# SiLPA.net
KiCad netlist of a schematic drawn in Altium Designer
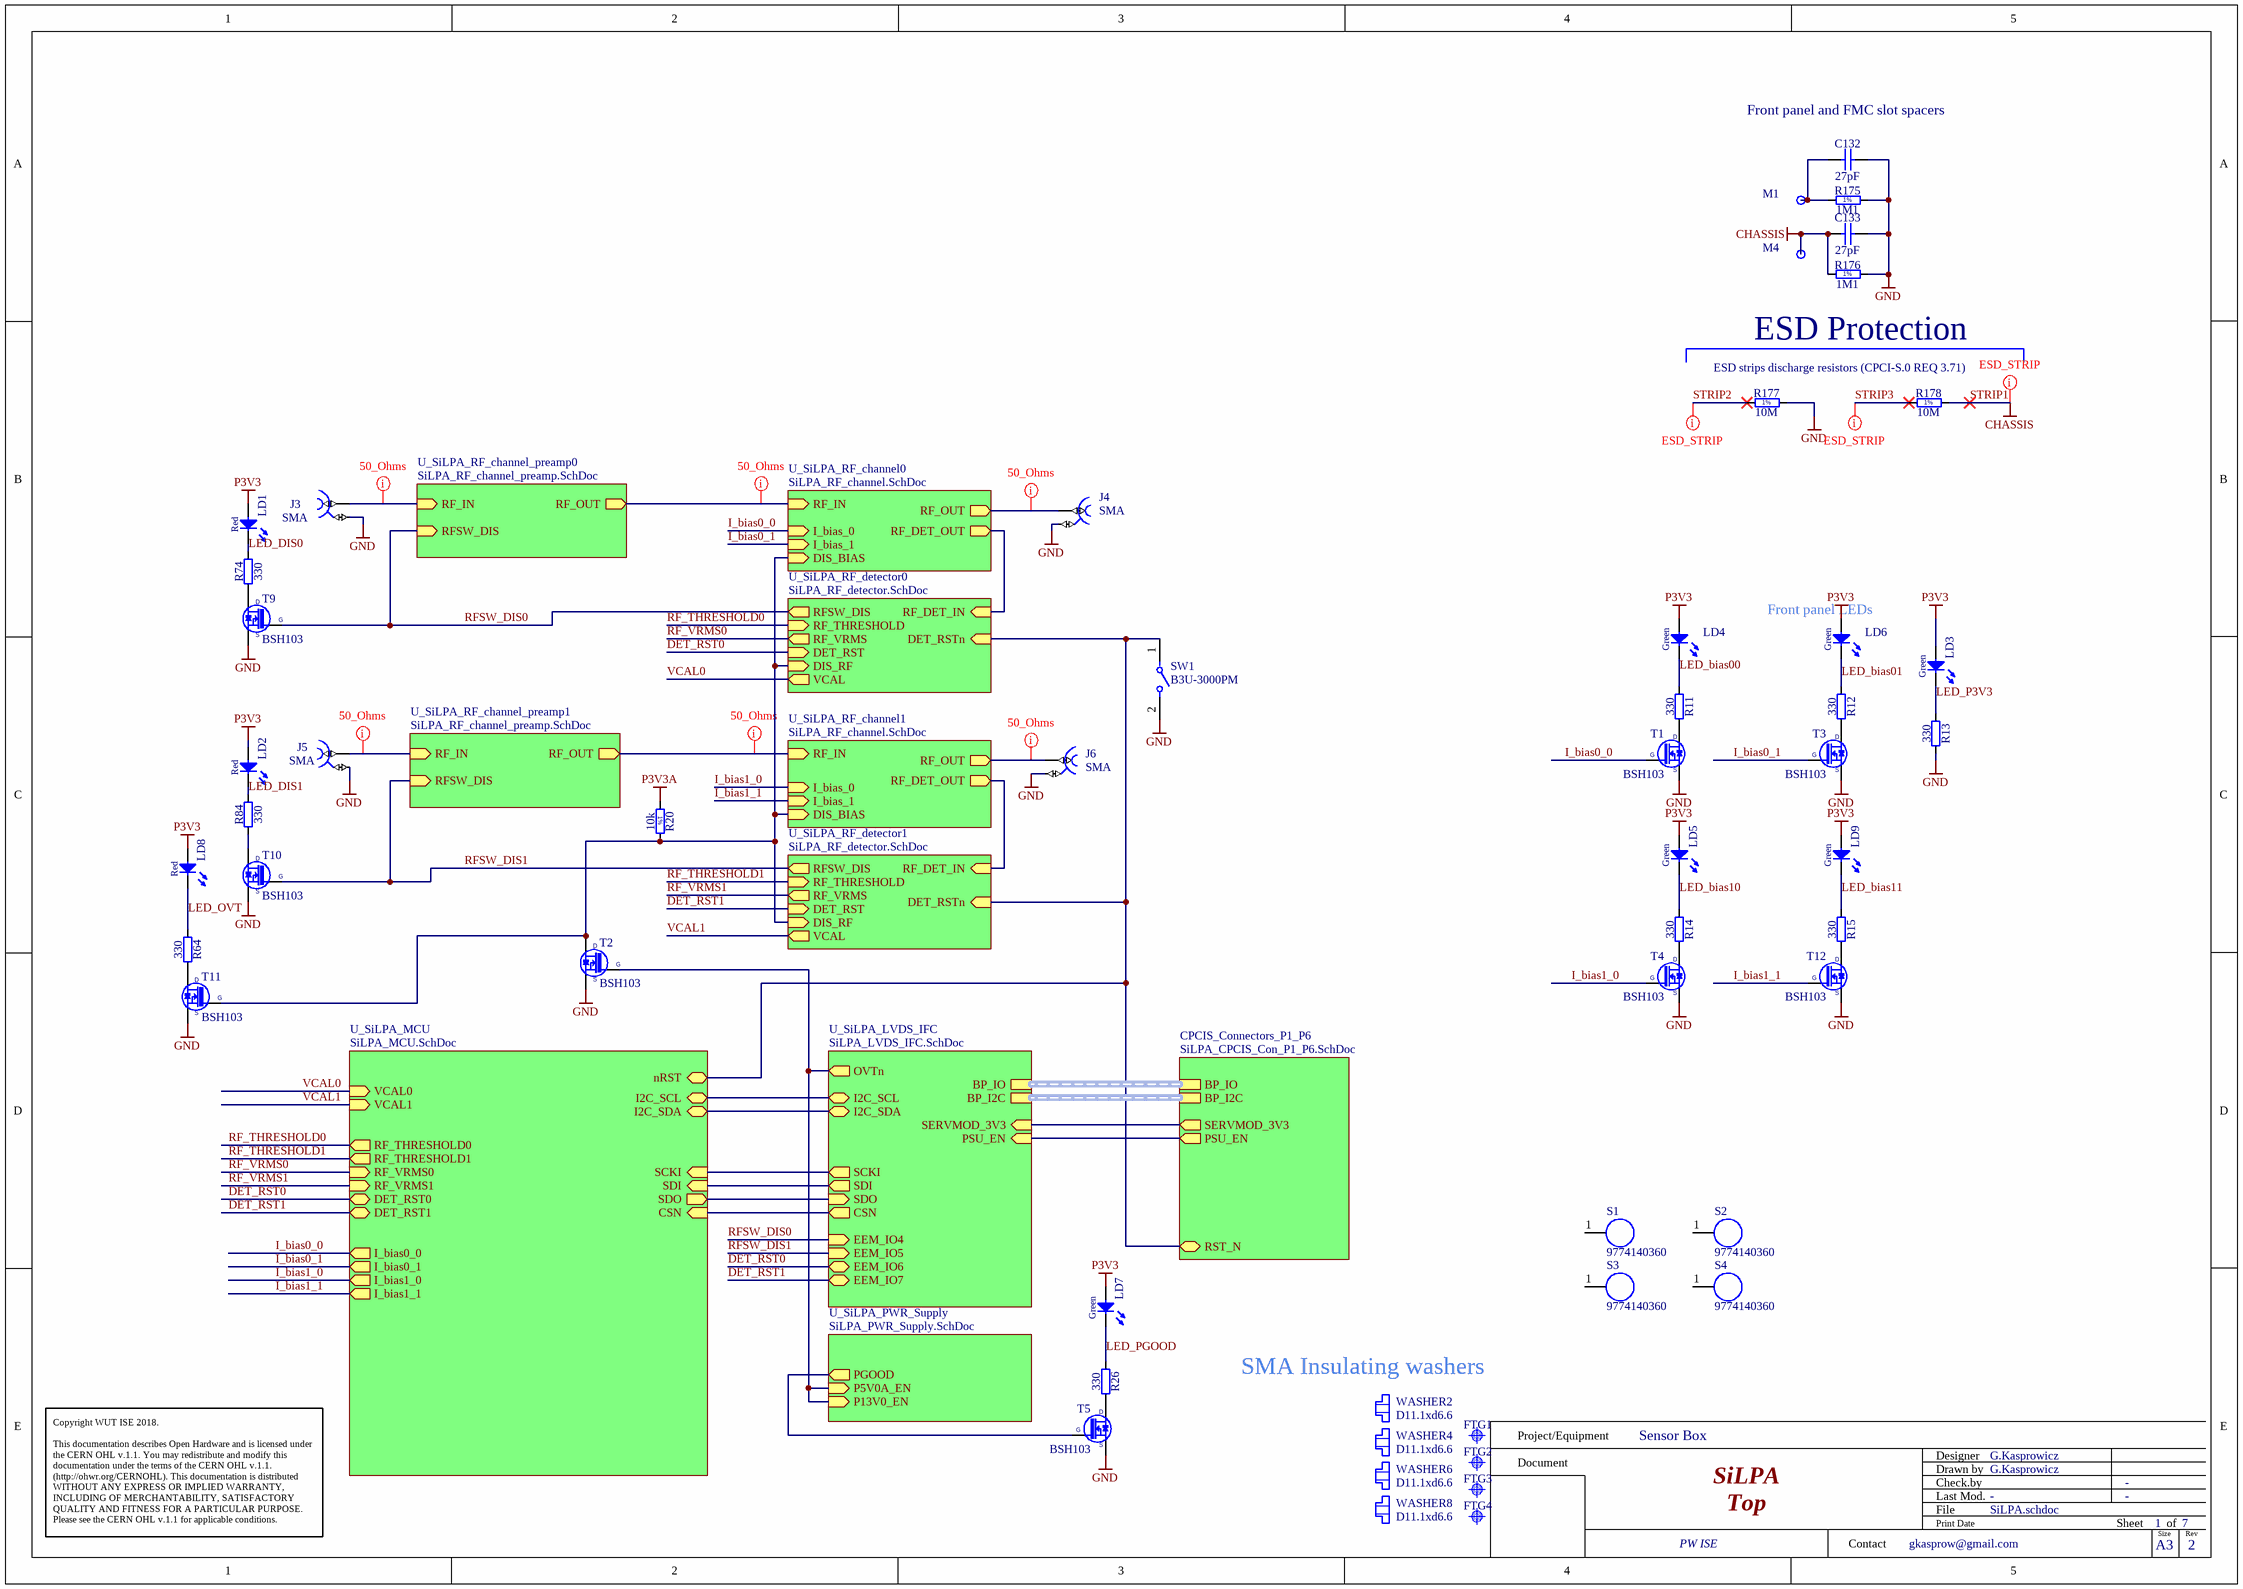
[diagram p0: SiLPA.schdoc]

(export (version "E")
  (design (tool "Eeschema 10.0.6"))
  (components
    (comp (ref "C132")
      (value "27pF")
      (footprint "CAPC1005X55N")
      (description "Non-polarised capacitor")
      (fields
        (field (name "PART NUMBER") "CC0402_27PF_50V_5%_C0G")
        (field (name "VOLTAGE") "50V")
        (field (name "AUTHOR") "CERN DEM JLC")
      )
      (libsource (lib "Capacitors") (part "Capacitor - non polarized"))
    )
    (comp (ref "C133")
      (value "27pF")
      (footprint "CAPC1005X55N")
      (description "Non-polarised capacitor")
      (fields
        (field (name "PART NUMBER") "CC0402_27PF_50V_5%_C0G")
        (field (name "VOLTAGE") "50V")
        (field (name "AUTHOR") "CERN DEM JLC")
      )
      (libsource (lib "Capacitors") (part "Capacitor - non polarized"))
    )
    (comp (ref "FTG1")
      (value "Use only in PCB")
      (footprint "FIDUCIAL_TOP_C100-200")
      (description "Fiducial Target")
      (fields (field (name "PART NUMBER") "FIDUCIAL_TARGET_C100-200") (field (name "AUTHOR") "CERN DEM JLC"))
      (libsource (lib "Eletro-mechanical") (part "Fiducial Target"))
    )
    (comp (ref "FTG2")
      (value "Use only in PCB")
      (footprint "FIDUCIAL_TOP_S100-200")
      (description "Fiducial Target")
      (fields (field (name "PART NUMBER") "FIDUCIAL_TARGET_S100-200") (field (name "AUTHOR") "CERN DEM JLC"))
      (libsource (lib "Eletro-mechanical") (part "Fiducial Target"))
    )
    (comp (ref "FTG3")
      (value "Use only in PCB")
      (footprint "FIDUCIAL_TOP_S100-200")
      (description "Fiducial Target")
      (fields (field (name "PART NUMBER") "FIDUCIAL_TARGET_S100-200") (field (name "AUTHOR") "CERN DEM JLC"))
      (libsource (lib "Eletro-mechanical") (part "Fiducial Target"))
    )
    (comp (ref "FTG4")
      (value "Use only in PCB")
      (footprint "FIDUCIAL_TOP_S100-200")
      (description "Fiducial Target")
      (fields (field (name "PART NUMBER") "FIDUCIAL_TARGET_S100-200") (field (name "AUTHOR") "CERN DEM JLC"))
      (libsource (lib "Eletro-mechanical") (part "Fiducial Target"))
    )
    (comp (ref "J3")
      (value "SMA")
      (footprint "DELOCK_65848")
      (description "50 Ohm Through Hole SMA Right Angle PCB Jack")
      (fields
        (field (name "PART NUMBER") "DELOCK_65848")
        (field (name "MANUFACTURER") "DELOCK")
        (field (name "AUTHOR") "GK")
      )
      (libsource (lib "Urukul") (part "DELOCK_65848"))
    )
    (comp (ref "J4")
      (value "SMA")
      (footprint "DELOCK_65848")
      (description "50 Ohm Through Hole SMA Right Angle PCB Jack")
      (fields
        (field (name "PART NUMBER") "DELOCK_65848")
        (field (name "MANUFACTURER") "DELOCK")
        (field (name "AUTHOR") "GK")
      )
      (libsource (lib "") (part "DELOCK_65848_1"))
    )
    (comp (ref "J5")
      (value "SMA")
      (footprint "DELOCK_65848")
      (description "50 Ohm Through Hole SMA Right Angle PCB Jack")
      (fields
        (field (name "PART NUMBER") "DELOCK_65848")
        (field (name "MANUFACTURER") "DELOCK")
        (field (name "AUTHOR") "GK")
      )
      (libsource (lib "Urukul") (part "DELOCK_65848"))
    )
    (comp (ref "J6")
      (value "SMA")
      (footprint "DELOCK_65848")
      (description "50 Ohm Through Hole SMA Right Angle PCB Jack")
      (fields
        (field (name "PART NUMBER") "DELOCK_65848")
        (field (name "MANUFACTURER") "DELOCK")
        (field (name "AUTHOR") "GK")
      )
      (libsource (lib "") (part "DELOCK_65848_1"))
    )
    (comp (ref "LD1")
      (value "Red")
      (footprint "LED_AVAGO_HSMC-C120")
      (description "LED Red 1C 2A")
      (fields
        (field (name "PART NUMBER") "LED_AVAGO_HSMC-C120")
        (field (name "MANUFACTURER") "AVAGO TECHNOLOGIES")
        (field (name "AUTHOR") "CERN DEM JMW")
      )
      (libsource (lib "ICs And Semiconductors") (part "LED Red 1C 2A"))
    )
    (comp (ref "LD2")
      (value "Red")
      (footprint "LED_AVAGO_HSMC-C120")
      (description "LED Red 1C 2A")
      (fields
        (field (name "PART NUMBER") "LED_AVAGO_HSMC-C120")
        (field (name "MANUFACTURER") "AVAGO TECHNOLOGIES")
        (field (name "AUTHOR") "CERN DEM JMW")
      )
      (libsource (lib "ICs And Semiconductors") (part "LED Red 1C 2A"))
    )
    (comp (ref "LD3")
      (value "Green")
      (footprint "LED_AVAGO_HSME-C120")
      (description "LED Green 1C 2A")
      (fields
        (field (name "PART NUMBER") "LED_AVAGO_HSME-C120")
        (field (name "MANUFACTURER") "AVAGO TECHNOLOGIES")
        (field (name "AUTHOR") "CERN DEM JMW")
      )
      (libsource (lib "ICs And Semiconductors") (part "LED Green 1C 2A"))
    )
    (comp (ref "LD4")
      (value "Green")
      (footprint "LED_AVAGO_HSME-C120")
      (description "LED Green 1C 2A")
      (fields
        (field (name "PART NUMBER") "LED_AVAGO_HSME-C120")
        (field (name "MANUFACTURER") "AVAGO TECHNOLOGIES")
        (field (name "AUTHOR") "CERN DEM JMW")
      )
      (libsource (lib "ICs And Semiconductors") (part "LED Green 1C 2A"))
    )
    (comp (ref "LD5")
      (value "Green")
      (footprint "LED_AVAGO_HSME-C120")
      (description "LED Green 1C 2A")
      (fields
        (field (name "PART NUMBER") "LED_AVAGO_HSME-C120")
        (field (name "MANUFACTURER") "AVAGO TECHNOLOGIES")
        (field (name "AUTHOR") "CERN DEM JMW")
      )
      (libsource (lib "ICs And Semiconductors") (part "LED Green 1C 2A"))
    )
    (comp (ref "LD6")
      (value "Green")
      (footprint "LED_AVAGO_HSME-C120")
      (description "LED Green 1C 2A")
      (fields
        (field (name "PART NUMBER") "LED_AVAGO_HSME-C120")
        (field (name "MANUFACTURER") "AVAGO TECHNOLOGIES")
        (field (name "AUTHOR") "CERN DEM JMW")
      )
      (libsource (lib "ICs And Semiconductors") (part "LED Green 1C 2A"))
    )
    (comp (ref "LD7")
      (value "Green")
      (footprint "LED_AVAGO_HSME-C120")
      (description "LED Green 1C 2A")
      (fields
        (field (name "PART NUMBER") "LED_AVAGO_HSME-C120")
        (field (name "MANUFACTURER") "AVAGO TECHNOLOGIES")
        (field (name "AUTHOR") "CERN DEM JMW")
      )
      (libsource (lib "ICs And Semiconductors") (part "LED Green 1C 2A"))
    )
    (comp (ref "LD8")
      (value "Red")
      (footprint "LED_AVAGO_HSMC-C120")
      (description "LED Red 1C 2A")
      (fields
        (field (name "PART NUMBER") "LED_AVAGO_HSMC-C120")
        (field (name "MANUFACTURER") "AVAGO TECHNOLOGIES")
        (field (name "AUTHOR") "CERN DEM JMW")
      )
      (libsource (lib "ICs And Semiconductors") (part "LED Red 1C 2A"))
    )
    (comp (ref "LD9")
      (value "Green")
      (footprint "LED_AVAGO_HSME-C120")
      (description "LED Green 1C 2A")
      (fields
        (field (name "PART NUMBER") "LED_AVAGO_HSME-C120")
        (field (name "MANUFACTURER") "AVAGO TECHNOLOGIES")
        (field (name "AUTHOR") "CERN DEM JMW")
      )
      (libsource (lib "ICs And Semiconductors") (part "LED Green 1C 2A"))
    )
    (comp (ref "M1")
      (value "Plated Hole")
      (footprint "MTG300_600")
      (description "Single Terminal Socket")
      (fields (field (name "PART NUMBER") "PLATED_HOLE3.0_PAD6.0") (field (name "AUTHOR") "CERN DEM JLC"))
      (libsource (lib "Eletro-mechanical") (part "Single Terminal Socket"))
    )
    (comp (ref "M4")
      (value "Plated Hole")
      (footprint "MTG300_600")
      (description "Single Terminal Socket")
      (fields (field (name "PART NUMBER") "PLATED_HOLE3.0_PAD6.0") (field (name "AUTHOR") "CERN DEM JLC"))
      (libsource (lib "Eletro-mechanical") (part "Single Terminal Socket"))
    )
    (comp (ref "R11")
      (value "330")
      (footprint "RESC1005X40N")
      (description "Resistor - 1%")
      (fields
        (field (name "PART NUMBER") "R0402_330R_1%_0.0625W_100PPM")
        (field (name "POWER") "0.0625W")
        (field (name "AUTHOR") "CERN DEM JLC")
      )
      (libsource (lib "") (part "Resistor - 1%_1"))
    )
    (comp (ref "R12")
      (value "330")
      (footprint "RESC1005X40N")
      (description "Resistor - 1%")
      (fields
        (field (name "PART NUMBER") "R0402_330R_1%_0.0625W_100PPM")
        (field (name "POWER") "0.0625W")
        (field (name "AUTHOR") "CERN DEM JLC")
      )
      (libsource (lib "") (part "Resistor - 1%_1"))
    )
    (comp (ref "R13")
      (value "330")
      (footprint "RESC1005X40N")
      (description "Resistor - 1%")
      (fields
        (field (name "PART NUMBER") "R0402_330R_1%_0.0625W_100PPM")
        (field (name "POWER") "0.0625W")
        (field (name "AUTHOR") "CERN DEM JLC")
      )
      (libsource (lib "") (part "Resistor - 1%_1"))
    )
    (comp (ref "R14")
      (value "330")
      (footprint "RESC1005X40N")
      (description "Resistor - 1%")
      (fields
        (field (name "PART NUMBER") "R0402_330R_1%_0.0625W_100PPM")
        (field (name "POWER") "0.0625W")
        (field (name "AUTHOR") "CERN DEM JLC")
      )
      (libsource (lib "") (part "Resistor - 1%_1"))
    )
    (comp (ref "R15")
      (value "330")
      (footprint "RESC1005X40N")
      (description "Resistor - 1%")
      (fields
        (field (name "PART NUMBER") "R0402_330R_1%_0.0625W_100PPM")
        (field (name "POWER") "0.0625W")
        (field (name "AUTHOR") "CERN DEM JLC")
      )
      (libsource (lib "") (part "Resistor - 1%_1"))
    )
    (comp (ref "R20")
      (value "10k")
      (footprint "RESC1005X40N")
      (description "Resistor - 1%")
      (fields
        (field (name "PART NUMBER") "R0402_10K_1%_0.0625W_100PPM")
        (field (name "POWER") "0.0625W")
        (field (name "AUTHOR") "CERN DEM JLC")
      )
      (libsource (lib "Resistors") (part "Resistor - 1%"))
    )
    (comp (ref "R26")
      (value "330")
      (footprint "RESC1005X40N")
      (description "Resistor - 1%")
      (fields
        (field (name "PART NUMBER") "R0402_330R_1%_0.0625W_100PPM")
        (field (name "POWER") "0.0625W")
        (field (name "AUTHOR") "CERN DEM JLC")
      )
      (libsource (lib "") (part "Resistor - 1%_1"))
    )
    (comp (ref "R64")
      (value "330")
      (footprint "RESC1005X40N")
      (description "Resistor - 1%")
      (fields
        (field (name "PART NUMBER") "R0402_330R_1%_0.0625W_100PPM")
        (field (name "POWER") "0.0625W")
        (field (name "AUTHOR") "CERN DEM JLC")
      )
      (libsource (lib "") (part "Resistor - 1%_1"))
    )
    (comp (ref "R74")
      (value "330")
      (footprint "RESC1005X40N")
      (description "Resistor - 1%")
      (fields
        (field (name "PART NUMBER") "R0402_330R_1%_0.0625W_100PPM")
        (field (name "POWER") "0.0625W")
        (field (name "AUTHOR") "CERN DEM JLC")
      )
      (libsource (lib "") (part "Resistor - 1%_1"))
    )
    (comp (ref "R84")
      (value "330")
      (footprint "RESC1005X40N")
      (description "Resistor - 1%")
      (fields
        (field (name "PART NUMBER") "R0402_330R_1%_0.0625W_100PPM")
        (field (name "POWER") "0.0625W")
        (field (name "AUTHOR") "CERN DEM JLC")
      )
      (libsource (lib "") (part "Resistor - 1%_1"))
    )
    (comp (ref "R175")
      (value "1M1")
      (footprint "RESC2012X60N")
      (description "Resistor - 1%")
      (fields
        (field (name "PART NUMBER") "R0805_1M1_1%_0.125W_100PPM")
        (field (name "POWER") "0.125W")
        (field (name "AUTHOR") "CERN DEM JLC")
      )
      (libsource (lib "Resistors") (part "Resistor - 1%"))
    )
    (comp (ref "R176")
      (value "1M1")
      (footprint "RESC2012X60N")
      (description "Resistor - 1%")
      (fields
        (field (name "PART NUMBER") "R0805_1M1_1%_0.125W_100PPM")
        (field (name "POWER") "0.125W")
        (field (name "AUTHOR") "CERN DEM JLC")
      )
      (libsource (lib "Resistors") (part "Resistor - 1%"))
    )
    (comp (ref "R177")
      (value "10M")
      (footprint "RESC2113X55N")
      (description "Resistor - 1%")
      (fields
        (field (name "PART NUMBER") "R0805_10M_1%_0.125W_100PPM_VISHAY_CRCW e3")
        (field (name "POWER") "0.125W")
        (field (name "AUTHOR") "CERN DEM BC")
      )
      (libsource (lib "Resistors") (part "Resistor - 1%"))
    )
    (comp (ref "R178")
      (value "10M")
      (footprint "RESC2113X55N")
      (description "Resistor - 1%")
      (fields
        (field (name "PART NUMBER") "R0805_10M_1%_0.125W_100PPM_VISHAY_CRCW e3")
        (field (name "POWER") "0.125W")
        (field (name "AUTHOR") "CERN DEM BC")
      )
      (libsource (lib "Resistors") (part "Resistor - 1%"))
    )
    (comp (ref "S1")
      (value "9774140360")
      (footprint "9774140360")
      (description "WA-SMSI SMD Steel Spacer with internal Thread")
      (fields (field (name "MANUFACTURER") "Wurth Elektronik") (field (name "CREATED BY") "Baojun Chen"))
      (libsource (lib "Altium_SMSI_SMT_STEEL_SPACER_M2_5_THREAD_INTERNAL_rev15a") (part "WA-SMSI,  9774140360"))
    )
    (comp (ref "S2")
      (value "9774140360")
      (footprint "9774140360")
      (description "WA-SMSI SMD Steel Spacer with internal Thread")
      (fields (field (name "MANUFACTURER") "Wurth Elektronik") (field (name "CREATED BY") "Baojun Chen"))
      (libsource (lib "Altium_SMSI_SMT_STEEL_SPACER_M2_5_THREAD_INTERNAL_rev15a") (part "WA-SMSI,  9774140360"))
    )
    (comp (ref "S3")
      (value "9774140360")
      (footprint "9774140360")
      (description "WA-SMSI SMD Steel Spacer with internal Thread")
      (fields (field (name "MANUFACTURER") "Wurth Elektronik") (field (name "CREATED BY") "Baojun Chen"))
      (libsource (lib "Altium_SMSI_SMT_STEEL_SPACER_M2_5_THREAD_INTERNAL_rev15a") (part "WA-SMSI,  9774140360"))
    )
    (comp (ref "S4")
      (value "9774140360")
      (footprint "9774140360")
      (description "WA-SMSI SMD Steel Spacer with internal Thread")
      (fields (field (name "MANUFACTURER") "Wurth Elektronik") (field (name "CREATED BY") "Baojun Chen"))
      (libsource (lib "Altium_SMSI_SMT_STEEL_SPACER_M2_5_THREAD_INTERNAL_rev15a") (part "WA-SMSI,  9774140360"))
    )
    (comp (ref "SW1")
      (value "B3U-3000PM")
      (footprint "FP-B3U-3000PM-MFG")
      (description "SWITCH TACTILE SPST-NO 0.05A 12V")
      (libsource (lib "Altium Content Vault") (part "bb27bde45df87f1f469753f287ef5ae"))
    )
    (comp (ref "T1")
      (value "BSH103")
      (footprint "SOT95P230X110-3N")
      (description "N-CHANNEL MOSFET WITH DIODE")
      (fields (field (name "MANUFACTURER") "NEXPERIA") (field (name "AUTHOR") "CERN DEM JLC"))
      (libsource (lib "ICs And Semiconductors") (part "N-MOSFET-D 1G 2S 3D"))
    )
    (comp (ref "T2")
      (value "BSH103")
      (footprint "SOT95P230X110-3N")
      (description "N-CHANNEL MOSFET WITH DIODE")
      (fields (field (name "MANUFACTURER") "NEXPERIA") (field (name "AUTHOR") "CERN DEM JLC"))
      (libsource (lib "") (part "N-MOSFET-D 1G 2S 3D_1"))
    )
    (comp (ref "T3")
      (value "BSH103")
      (footprint "SOT95P230X110-3N")
      (description "N-CHANNEL MOSFET WITH DIODE")
      (fields (field (name "MANUFACTURER") "NEXPERIA") (field (name "AUTHOR") "CERN DEM JLC"))
      (libsource (lib "ICs And Semiconductors") (part "N-MOSFET-D 1G 2S 3D"))
    )
    (comp (ref "T4")
      (value "BSH103")
      (footprint "SOT95P230X110-3N")
      (description "N-CHANNEL MOSFET WITH DIODE")
      (fields (field (name "MANUFACTURER") "NEXPERIA") (field (name "AUTHOR") "CERN DEM JLC"))
      (libsource (lib "ICs And Semiconductors") (part "N-MOSFET-D 1G 2S 3D"))
    )
    (comp (ref "T5")
      (value "BSH103")
      (footprint "SOT95P230X110-3N")
      (description "N-CHANNEL MOSFET WITH DIODE")
      (fields (field (name "MANUFACTURER") "NEXPERIA") (field (name "AUTHOR") "CERN DEM JLC"))
      (libsource (lib "ICs And Semiconductors") (part "N-MOSFET-D 1G 2S 3D"))
    )
    (comp (ref "T9")
      (value "BSH103")
      (footprint "SOT95P230X110-3N")
      (description "N-CHANNEL MOSFET WITH DIODE")
      (fields (field (name "MANUFACTURER") "NEXPERIA") (field (name "AUTHOR") "CERN DEM JLC"))
      (libsource (lib "") (part "N-MOSFET-D 1G 2S 3D_1"))
    )
    (comp (ref "T10")
      (value "BSH103")
      (footprint "SOT95P230X110-3N")
      (description "N-CHANNEL MOSFET WITH DIODE")
      (fields (field (name "MANUFACTURER") "NEXPERIA") (field (name "AUTHOR") "CERN DEM JLC"))
      (libsource (lib "") (part "N-MOSFET-D 1G 2S 3D_1"))
    )
    (comp (ref "T11")
      (value "BSH103")
      (footprint "SOT95P230X110-3N")
      (description "N-CHANNEL MOSFET WITH DIODE")
      (fields (field (name "MANUFACTURER") "NEXPERIA") (field (name "AUTHOR") "CERN DEM JLC"))
      (libsource (lib "") (part "N-MOSFET-D 1G 2S 3D_1"))
    )
    (comp (ref "T12")
      (value "BSH103")
      (footprint "SOT95P230X110-3N")
      (description "N-CHANNEL MOSFET WITH DIODE")
      (fields (field (name "MANUFACTURER") "NEXPERIA") (field (name "AUTHOR") "CERN DEM JLC"))
      (libsource (lib "ICs And Semiconductors") (part "N-MOSFET-D 1G 2S 3D"))
    )
    (comp (ref "WASHER2")
      (value "D11.1xd6.6")
      (footprint "Keystone_7687")
      (description "SMA_Shoulder Washer")
      (fields (field (name "PART NUMBER") "custom 3D") (field (name "AUTHOR") "GK"))
      (libsource (lib "LIBRARY_SCH") (part "Keystone_7687"))
    )
    (comp (ref "WASHER4")
      (value "D11.1xd6.6")
      (footprint "Keystone_7687")
      (description "SMA_Shoulder Washer")
      (fields (field (name "PART NUMBER") "custom 3D") (field (name "AUTHOR") "GK"))
      (libsource (lib "LIBRARY_SCH") (part "Keystone_7687"))
    )
    (comp (ref "WASHER6")
      (value "D11.1xd6.6")
      (footprint "Keystone_7687")
      (description "SMA_Shoulder Washer")
      (fields (field (name "PART NUMBER") "custom 3D") (field (name "AUTHOR") "GK"))
      (libsource (lib "LIBRARY_SCH") (part "Keystone_7687"))
    )
    (comp (ref "WASHER8")
      (value "D11.1xd6.6")
      (footprint "Keystone_7687")
      (description "SMA_Shoulder Washer")
      (fields (field (name "PART NUMBER") "custom 3D") (field (name "AUTHOR") "GK"))
      (libsource (lib "LIBRARY_SCH") (part "Keystone_7687"))
    )
  )
  (nets
    (net (code "6") (name "/DET_RSTn") (class "Default")
      (node (ref "SW1") (pin "1") (pinfunction "1_1") (pintype "passive"))
    )
    (net (code "7") (name "/DIS_BIAS") (class "Default")
      (node (ref "R20") (pin "2") (pinfunction "2_2") (pintype "passive"))
      (node (ref "T11") (pin "1") (pinfunction "G_1") (pintype "passive"))
      (node (ref "T2") (pin "3") (pinfunction "D_3") (pintype "passive"))
    )
    (net (code "10") (name "/I_bias0_0") (class "Default")
      (node (ref "T1") (pin "1") (pinfunction "G_1") (pintype "passive"))
    )
    (net (code "11") (name "/I_bias0_1") (class "Default")
      (node (ref "T3") (pin "1") (pinfunction "G_1") (pintype "passive"))
    )
    (net (code "12") (name "/I_bias1_0") (class "Default")
      (node (ref "T4") (pin "1") (pinfunction "G_1") (pintype "passive"))
    )
    (net (code "13") (name "/I_bias1_1") (class "Default")
      (node (ref "T12") (pin "1") (pinfunction "G_1") (pintype "passive"))
    )
    (net (code "14") (name "/LED_DIS0") (class "Default")
      (node (ref "LD1") (pin "1") (pinfunction "C_1") (pintype "passive"))
      (node (ref "R74") (pin "1") (pinfunction "1_1") (pintype "passive"))
    )
    (net (code "15") (name "/LED_DIS1") (class "Default")
      (node (ref "LD2") (pin "1") (pinfunction "C_1") (pintype "passive"))
      (node (ref "R84") (pin "1") (pinfunction "1_1") (pintype "passive"))
    )
    (net (code "16") (name "/LED_OVT") (class "Default")
      (node (ref "LD8") (pin "1") (pinfunction "C_1") (pintype "passive"))
      (node (ref "R64") (pin "1") (pinfunction "1_1") (pintype "passive"))
    )
    (net (code "17") (name "/LED_P3V3") (class "Default")
      (node (ref "LD3") (pin "1") (pinfunction "C_1") (pintype "passive"))
      (node (ref "R13") (pin "1") (pinfunction "1_1") (pintype "passive"))
    )
    (net (code "18") (name "/LED_PGOOD") (class "Default")
      (node (ref "LD7") (pin "1") (pinfunction "C_1") (pintype "passive"))
      (node (ref "R26") (pin "1") (pinfunction "1_1") (pintype "passive"))
    )
    (net (code "19") (name "/LED_bias00") (class "Default")
      (node (ref "LD4") (pin "1") (pinfunction "C_1") (pintype "passive"))
      (node (ref "R11") (pin "1") (pinfunction "1_1") (pintype "passive"))
    )
    (net (code "20") (name "/LED_bias01") (class "Default")
      (node (ref "LD6") (pin "1") (pinfunction "C_1") (pintype "passive"))
      (node (ref "R12") (pin "1") (pinfunction "1_1") (pintype "passive"))
    )
    (net (code "21") (name "/LED_bias10") (class "Default")
      (node (ref "LD5") (pin "1") (pinfunction "C_1") (pintype "passive"))
      (node (ref "R14") (pin "1") (pinfunction "1_1") (pintype "passive"))
    )
    (net (code "22") (name "/LED_bias11") (class "Default")
      (node (ref "LD9") (pin "1") (pinfunction "C_1") (pintype "passive"))
      (node (ref "R15") (pin "1") (pinfunction "1_1") (pintype "passive"))
    )
    (net (code "23") (name "/OVTn") (class "Default")
      (node (ref "T2") (pin "1") (pinfunction "G_1") (pintype "passive"))
    )
    (net (code "24") (name "/PGOOD") (class "Default")
      (node (ref "T5") (pin "1") (pinfunction "G_1") (pintype "passive"))
    )
    (net (code "26") (name "/RFSW_DIS0") (class "Default")
      (node (ref "T9") (pin "1") (pinfunction "G_1") (pintype "passive"))
    )
    (net (code "27") (name "/RFSW_DIS1") (class "Default")
      (node (ref "T10") (pin "1") (pinfunction "G_1") (pintype "passive"))
    )
    (net (code "30") (name "/RF_IN") (class "Default")
      (node (ref "J3") (pin "1") (pinfunction "1_1") (pintype "bidirectional"))
    )
    (net (code "31") (name "/RF_IN_1") (class "Default")
      (node (ref "J5") (pin "1") (pinfunction "1_1") (pintype "bidirectional"))
    )
    (net (code "32") (name "/RF_OUT") (class "Default")
      (node (ref "J6") (pin "1") (pinfunction "1_1") (pintype "bidirectional"))
    )
    (net (code "35") (name "/RF_OUT_3") (class "Default")
      (node (ref "J4") (pin "1") (pinfunction "1_1") (pintype "bidirectional"))
    )
    (net (code "45") (name "/STRIP2") (class "Default")
      (node (ref "R177") (pin "1") (pinfunction "1_1") (pintype "passive+no_connect"))
    )
    (net (code "46") (name "/STRIP3") (class "Default")
      (node (ref "R178") (pin "1") (pinfunction "1_1") (pintype "passive+no_connect"))
    )
    (net (code "49") (name "CHASSIS") (class "Default")
      (node (ref "C133") (pin "1") (pinfunction "1_1") (pintype "passive"))
      (node (ref "M4") (pin "1") (pinfunction "1_1") (pintype "bidirectional"))
      (node (ref "R176") (pin "1") (pinfunction "1_1") (pintype "passive"))
      (node (ref "R178") (pin "2") (pinfunction "2_2") (pintype "passive"))
    )
    (net (code "50") (name "GND") (class "Default")
      (node (ref "C132") (pin "2") (pinfunction "2_2") (pintype "passive"))
      (node (ref "C133") (pin "2") (pinfunction "2_2") (pintype "passive"))
      (node (ref "J3") (pin "2") (pinfunction "2_2") (pintype "bidirectional"))
      (node (ref "J4") (pin "2") (pinfunction "2_2") (pintype "bidirectional"))
      (node (ref "J5") (pin "2") (pinfunction "2_2") (pintype "bidirectional"))
      (node (ref "J6") (pin "2") (pinfunction "2_2") (pintype "bidirectional"))
      (node (ref "R13") (pin "2") (pinfunction "2_2") (pintype "passive"))
      (node (ref "R175") (pin "2") (pinfunction "2_2") (pintype "passive"))
      (node (ref "R176") (pin "2") (pinfunction "2_2") (pintype "passive"))
      (node (ref "R177") (pin "2") (pinfunction "2_2") (pintype "passive"))
      (node (ref "SW1") (pin "2") (pinfunction "2_2") (pintype "passive"))
      (node (ref "T1") (pin "2") (pinfunction "S_2") (pintype "passive"))
      (node (ref "T10") (pin "2") (pinfunction "S_2") (pintype "passive"))
      (node (ref "T11") (pin "2") (pinfunction "S_2") (pintype "passive"))
      (node (ref "T12") (pin "2") (pinfunction "S_2") (pintype "passive"))
      (node (ref "T2") (pin "2") (pinfunction "S_2") (pintype "passive"))
      (node (ref "T3") (pin "2") (pinfunction "S_2") (pintype "passive"))
      (node (ref "T4") (pin "2") (pinfunction "S_2") (pintype "passive"))
      (node (ref "T5") (pin "2") (pinfunction "S_2") (pintype "passive"))
      (node (ref "T9") (pin "2") (pinfunction "S_2") (pintype "passive"))
    )
    (net (code "51") (name "Net-(C132-Pad1)") (class "Default")
      (node (ref "C132") (pin "1") (pinfunction "1_1") (pintype "passive"))
      (node (ref "M1") (pin "1") (pinfunction "1_1") (pintype "bidirectional"))
      (node (ref "R175") (pin "1") (pinfunction "1_1") (pintype "passive"))
    )
    (net (code "52") (name "Net-(T1-D)") (class "Default")
      (node (ref "R11") (pin "2") (pinfunction "2_2") (pintype "passive"))
      (node (ref "T1") (pin "3") (pinfunction "D_3") (pintype "passive"))
    )
    (net (code "53") (name "Net-(T3-D)") (class "Default")
      (node (ref "R12") (pin "2") (pinfunction "2_2") (pintype "passive"))
      (node (ref "T3") (pin "3") (pinfunction "D_3") (pintype "passive"))
    )
    (net (code "54") (name "Net-(T4-D)") (class "Default")
      (node (ref "R14") (pin "2") (pinfunction "2_2") (pintype "passive"))
      (node (ref "T4") (pin "3") (pinfunction "D_3") (pintype "passive"))
    )
    (net (code "55") (name "Net-(T5-D)") (class "Default")
      (node (ref "R26") (pin "2") (pinfunction "2_2") (pintype "passive"))
      (node (ref "T5") (pin "3") (pinfunction "D_3") (pintype "passive"))
    )
    (net (code "56") (name "Net-(T9-D)") (class "Default")
      (node (ref "R74") (pin "2") (pinfunction "2_2") (pintype "passive"))
      (node (ref "T9") (pin "3") (pinfunction "D_3") (pintype "passive"))
    )
    (net (code "57") (name "Net-(T10-D)") (class "Default")
      (node (ref "R84") (pin "2") (pinfunction "2_2") (pintype "passive"))
      (node (ref "T10") (pin "3") (pinfunction "D_3") (pintype "passive"))
    )
    (net (code "58") (name "Net-(T11-D)") (class "Default")
      (node (ref "R64") (pin "2") (pinfunction "2_2") (pintype "passive"))
      (node (ref "T11") (pin "3") (pinfunction "D_3") (pintype "passive"))
    )
    (net (code "59") (name "Net-(T12-D)") (class "Default")
      (node (ref "R15") (pin "2") (pinfunction "2_2") (pintype "passive"))
      (node (ref "T12") (pin "3") (pinfunction "D_3") (pintype "passive"))
    )
    (net (code "60") (name "P3V3") (class "Default")
      (node (ref "LD1") (pin "2") (pinfunction "A_2") (pintype "passive"))
      (node (ref "LD2") (pin "2") (pinfunction "A_2") (pintype "passive"))
      (node (ref "LD3") (pin "2") (pinfunction "A_2") (pintype "passive"))
      (node (ref "LD4") (pin "2") (pinfunction "A_2") (pintype "passive"))
      (node (ref "LD5") (pin "2") (pinfunction "A_2") (pintype "passive"))
      (node (ref "LD6") (pin "2") (pinfunction "A_2") (pintype "passive"))
      (node (ref "LD7") (pin "2") (pinfunction "A_2") (pintype "passive"))
      (node (ref "LD8") (pin "2") (pinfunction "A_2") (pintype "passive"))
      (node (ref "LD9") (pin "2") (pinfunction "A_2") (pintype "passive"))
    )
    (net (code "61") (name "P3V3A") (class "Default")
      (node (ref "R20") (pin "1") (pinfunction "1_1") (pintype "passive"))
    )
    (net (code "62") (name "unconnected-(S1-Pad1)") (class "Default")
      (node (ref "S1") (pin "1") (pinfunction "1_1") (pintype "passive"))
    )
    (net (code "63") (name "unconnected-(S2-Pad1)") (class "Default")
      (node (ref "S2") (pin "1") (pinfunction "1_1") (pintype "passive"))
    )
    (net (code "64") (name "unconnected-(S3-Pad1)") (class "Default")
      (node (ref "S3") (pin "1") (pinfunction "1_1") (pintype "passive"))
    )
    (net (code "65") (name "unconnected-(S4-Pad1)") (class "Default")
      (node (ref "S4") (pin "1") (pinfunction "1_1") (pintype "passive"))
    )
  )
)
